# shupito.net
KiCad netlist of a schematic drawn in EAGLE
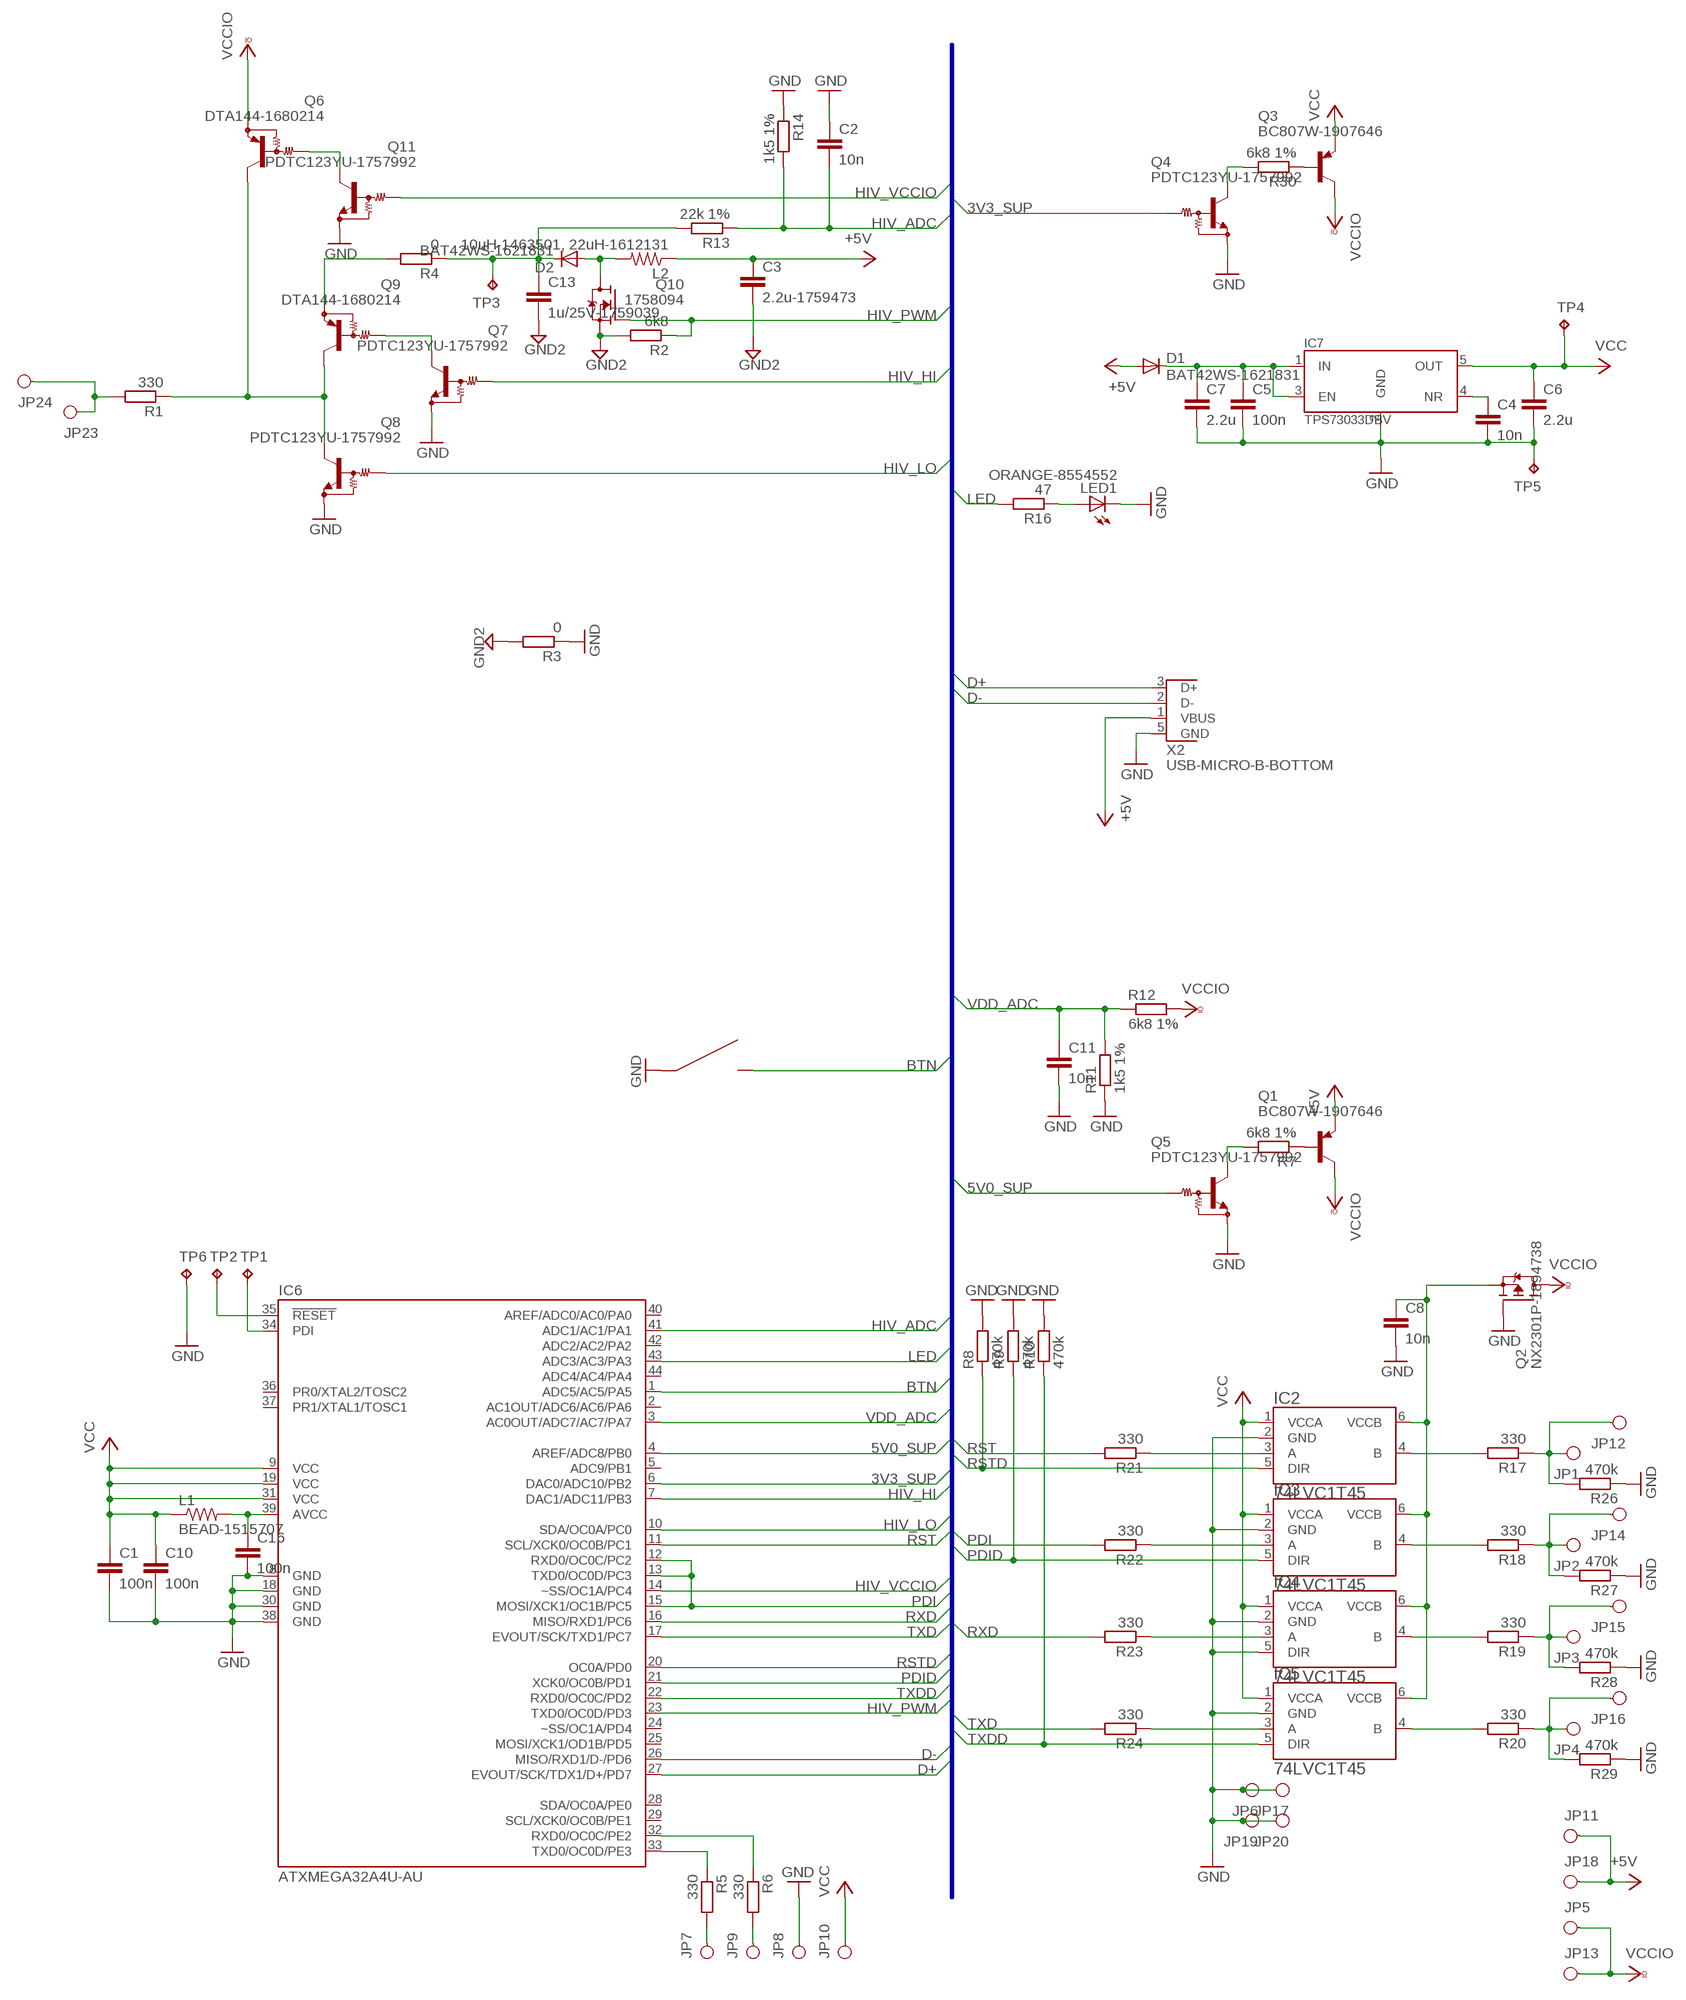
[diagram p0: schematic, sheet 1]

(export (version "E")
  (design (tool "Eeschema 10.0.6"))
  (components
    (comp (ref "C1")
      (value "100n")
      (footprint "eagle-import:C0603K")
      (libsource (lib "eagle-import") (part "C-EUC0603K"))
    )
    (comp (ref "C2")
      (value "10n")
      (footprint "eagle-import:C0603K")
      (libsource (lib "eagle-import") (part "C-EUC0603K"))
    )
    (comp (ref "C3")
      (value "2.2u-1759473")
      (footprint "eagle-import:C0603K")
      (libsource (lib "eagle-import") (part "C-EUC0603K"))
    )
    (comp (ref "C4")
      (value "10n")
      (footprint "eagle-import:C0603K")
      (libsource (lib "eagle-import") (part "C-EUC0603K"))
    )
    (comp (ref "C5")
      (value "100n")
      (footprint "eagle-import:C0603K")
      (libsource (lib "eagle-import") (part "C-EUC0603K"))
    )
    (comp (ref "C6")
      (value "2.2u")
      (footprint "eagle-import:C0603K")
      (libsource (lib "eagle-import") (part "C-EUC0603K"))
    )
    (comp (ref "C7")
      (value "2.2u")
      (footprint "eagle-import:C0603K")
      (libsource (lib "eagle-import") (part "C-EUC0603K"))
    )
    (comp (ref "C8")
      (value "10n")
      (footprint "eagle-import:C0603K")
      (libsource (lib "eagle-import") (part "C-EUC0603K"))
    )
    (comp (ref "C10")
      (value "100n")
      (footprint "eagle-import:C0603K")
      (libsource (lib "eagle-import") (part "C-EUC0603K"))
    )
    (comp (ref "C11")
      (value "10n")
      (footprint "eagle-import:C0603K")
      (libsource (lib "eagle-import") (part "C-EUC0603K"))
    )
    (comp (ref "C13")
      (value "1u/25V-1759039")
      (footprint "eagle-import:C0603K")
      (libsource (lib "eagle-import") (part "C-EUC0603K"))
    )
    (comp (ref "C16")
      (value "100n")
      (footprint "eagle-import:C0603K")
      (libsource (lib "eagle-import") (part "C-EUC0603K"))
    )
    (comp (ref "D1")
      (value "BAT42WS-1621831")
      (footprint "eagle-import:SOD323")
      (libsource (lib "eagle-import") (part "DIODE-SOD323"))
    )
    (comp (ref "D2")
      (value "BAT42WS-1621831")
      (footprint "eagle-import:SOD323")
      (libsource (lib "eagle-import") (part "DIODE-SOD323"))
    )
    (comp (ref "IC2")
      (value "74LVC1T45")
      (footprint "eagle-import:SOT236")
      (libsource (lib "eagle-import") (part "741T45DBVLVC"))
    )
    (comp (ref "IC3")
      (value "74LVC1T45")
      (footprint "eagle-import:SOT236")
      (libsource (lib "eagle-import") (part "741T45DBVLVC"))
    )
    (comp (ref "IC4")
      (value "74LVC1T45")
      (footprint "eagle-import:SOT236")
      (libsource (lib "eagle-import") (part "741T45DBVLVC"))
    )
    (comp (ref "IC5")
      (value "74LVC1T45")
      (footprint "eagle-import:SOT236")
      (libsource (lib "eagle-import") (part "741T45DBVLVC"))
    )
    (comp (ref "IC6")
      (value "ATXMEGA32A4U-AU")
      (footprint "eagle-import:TQFP44")
      (libsource (lib "eagle-import") (part "ATXMEGAA4U-AU32"))
    )
    (comp (ref "IC7")
      (value "TPS73033DBV")
      (footprint "eagle-import:SOT23-DBV")
      (libsource (lib "eagle-import") (part "TPS73033DBV"))
    )
    (comp (ref "JP1")
      (value "PINH1X01SMD")
      (footprint "eagle-import:PINH1X01SMD")
      (libsource (lib "eagle-import") (part "PINH1X01SMD"))
    )
    (comp (ref "JP2")
      (value "PINH1X01SMD")
      (footprint "eagle-import:PINH1X01SMD")
      (libsource (lib "eagle-import") (part "PINH1X01SMD"))
    )
    (comp (ref "JP3")
      (value "PINH1X01SMD")
      (footprint "eagle-import:PINH1X01SMD")
      (libsource (lib "eagle-import") (part "PINH1X01SMD"))
    )
    (comp (ref "JP4")
      (value "PINH1X01SMD")
      (footprint "eagle-import:PINH1X01SMD")
      (libsource (lib "eagle-import") (part "PINH1X01SMD"))
    )
    (comp (ref "JP5")
      (value "PINH1X01SMD")
      (footprint "eagle-import:PINH1X01SMD")
      (libsource (lib "eagle-import") (part "PINH1X01SMD"))
    )
    (comp (ref "JP6")
      (value "PINH1X01SMD")
      (footprint "eagle-import:PINH1X01SMD")
      (libsource (lib "eagle-import") (part "PINH1X01SMD"))
    )
    (comp (ref "JP7")
      (value "PINH1X01SMD")
      (footprint "eagle-import:PINH1X01SMD")
      (libsource (lib "eagle-import") (part "PINH1X01SMD"))
    )
    (comp (ref "JP8")
      (value "PINH1X01SMD")
      (footprint "eagle-import:PINH1X01SMD")
      (libsource (lib "eagle-import") (part "PINH1X01SMD"))
    )
    (comp (ref "JP9")
      (value "PINH1X01SMD")
      (footprint "eagle-import:PINH1X01SMD")
      (libsource (lib "eagle-import") (part "PINH1X01SMD"))
    )
    (comp (ref "JP10")
      (value "PINH1X01SMD")
      (footprint "eagle-import:PINH1X01SMD")
      (libsource (lib "eagle-import") (part "PINH1X01SMD"))
    )
    (comp (ref "JP11")
      (value "PINH1X01SMD")
      (footprint "eagle-import:PINH1X01SMD")
      (libsource (lib "eagle-import") (part "PINH1X01SMD"))
    )
    (comp (ref "JP12")
      (value "PINH1X01SMD")
      (footprint "eagle-import:PINH1X01SMD")
      (libsource (lib "eagle-import") (part "PINH1X01SMD"))
    )
    (comp (ref "JP13")
      (value "PINH1X01SMD")
      (footprint "eagle-import:PINH1X01SMD")
      (libsource (lib "eagle-import") (part "PINH1X01SMD"))
    )
    (comp (ref "JP14")
      (value "PINH1X01SMD")
      (footprint "eagle-import:PINH1X01SMD")
      (libsource (lib "eagle-import") (part "PINH1X01SMD"))
    )
    (comp (ref "JP15")
      (value "PINH1X01SMD")
      (footprint "eagle-import:PINH1X01SMD")
      (libsource (lib "eagle-import") (part "PINH1X01SMD"))
    )
    (comp (ref "JP16")
      (value "PINH1X01SMD")
      (footprint "eagle-import:PINH1X01SMD")
      (libsource (lib "eagle-import") (part "PINH1X01SMD"))
    )
    (comp (ref "JP17")
      (value "PINH1X01SMD")
      (footprint "eagle-import:PINH1X01SMD")
      (libsource (lib "eagle-import") (part "PINH1X01SMD"))
    )
    (comp (ref "JP18")
      (value "PINH1X01SMD")
      (footprint "eagle-import:PINH1X01SMD")
      (libsource (lib "eagle-import") (part "PINH1X01SMD"))
    )
    (comp (ref "JP19")
      (value "PINH1X01SMD")
      (footprint "eagle-import:PINH1X01SMD")
      (libsource (lib "eagle-import") (part "PINH1X01SMD"))
    )
    (comp (ref "JP20")
      (value "PINH1X01SMD")
      (footprint "eagle-import:PINH1X01SMD")
      (libsource (lib "eagle-import") (part "PINH1X01SMD"))
    )
    (comp (ref "JP23")
      (value "PINH1X01SMD")
      (footprint "eagle-import:PINH1X01SMD")
      (libsource (lib "eagle-import") (part "PINH1X01SMD"))
    )
    (comp (ref "JP24")
      (value "PINH1X01SMD")
      (footprint "eagle-import:PINH1X01SMD")
      (libsource (lib "eagle-import") (part "PINH1X01SMD"))
    )
    (comp (ref "L1")
      (value "BEAD-1515707")
      (footprint "eagle-import:R0603")
      (libsource (lib "eagle-import") (part "R-US_R0603"))
    )
    (comp (ref "L2")
      (value "10uH-1463501, 22uH-1612131")
      (footprint "eagle-import:R0805")
      (libsource (lib "eagle-import") (part "R-US_R0805"))
    )
    (comp (ref "LED1")
      (value "ORANGE-8554552")
      (footprint "eagle-import:CHIPLED_0603")
      (libsource (lib "eagle-import") (part "LEDCHIPLED_0603"))
    )
    (comp (ref "Q1")
      (value "BC807W-1907646")
      (footprint "eagle-import:SOT323-BEC")
      (libsource (lib "eagle-import") (part "BC807W"))
    )
    (comp (ref "Q2")
      (value "NX2301P-1894738")
      (footprint "eagle-import:SOT23")
      (libsource (lib "eagle-import") (part "P-MOSFET-SOT23-GSD"))
    )
    (comp (ref "Q3")
      (value "BC807W-1907646")
      (footprint "eagle-import:SOT323-BEC")
      (libsource (lib "eagle-import") (part "BC807W"))
    )
    (comp (ref "Q4")
      (value "PDTC123YU-1757992")
      (footprint "eagle-import:SOT323")
      (libsource (lib "eagle-import") (part "NPN-BIAS-SOT323-BEC"))
    )
    (comp (ref "Q5")
      (value "PDTC123YU-1757992")
      (footprint "eagle-import:SOT323")
      (libsource (lib "eagle-import") (part "NPN-BIAS-SOT323-BEC"))
    )
    (comp (ref "Q6")
      (value "DTA144-1680214")
      (footprint "eagle-import:SOT323")
      (libsource (lib "eagle-import") (part "PNP-BIAS-SOT323-BEC"))
    )
    (comp (ref "Q7")
      (value "PDTC123YU-1757992")
      (footprint "eagle-import:SOT323")
      (libsource (lib "eagle-import") (part "NPN-BIAS-SOT323-BEC"))
    )
    (comp (ref "Q8")
      (value "PDTC123YU-1757992")
      (footprint "eagle-import:SOT323")
      (libsource (lib "eagle-import") (part "NPN-BIAS-SOT323-BEC"))
    )
    (comp (ref "Q9")
      (value "DTA144-1680214")
      (footprint "eagle-import:SOT323")
      (libsource (lib "eagle-import") (part "PNP-BIAS-SOT323-BEC"))
    )
    (comp (ref "Q10")
      (value "1758094")
      (footprint "eagle-import:SOT323")
      (libsource (lib "eagle-import") (part "N-MOSFET-SOT323-GSD"))
    )
    (comp (ref "Q11")
      (value "PDTC123YU-1757992")
      (footprint "eagle-import:SOT323")
      (libsource (lib "eagle-import") (part "NPN-BIAS-SOT323-BEC"))
    )
    (comp (ref "R1")
      (value "330")
      (footprint "eagle-import:R0603")
      (libsource (lib "eagle-import") (part "R-EU_R0603"))
    )
    (comp (ref "R2")
      (value "6k8")
      (footprint "eagle-import:R0603")
      (libsource (lib "eagle-import") (part "R-EU_R0603"))
    )
    (comp (ref "R3")
      (value "0")
      (footprint "eagle-import:R1206")
      (libsource (lib "eagle-import") (part "R-EU_R1206"))
    )
    (comp (ref "R4")
      (value "0")
      (footprint "eagle-import:R1206")
      (libsource (lib "eagle-import") (part "R-EU_R1206"))
    )
    (comp (ref "R5")
      (value "330")
      (footprint "eagle-import:R0603")
      (libsource (lib "eagle-import") (part "R-EU_R0603"))
    )
    (comp (ref "R6")
      (value "330")
      (footprint "eagle-import:R0603")
      (libsource (lib "eagle-import") (part "R-EU_R0603"))
    )
    (comp (ref "R7")
      (value "6k8 1%")
      (footprint "eagle-import:R0603")
      (libsource (lib "eagle-import") (part "R-EU_R0603"))
    )
    (comp (ref "R8")
      (value "470k")
      (footprint "eagle-import:R0603")
      (libsource (lib "eagle-import") (part "R-EU_R0603"))
    )
    (comp (ref "R9")
      (value "470k")
      (footprint "eagle-import:R0603")
      (libsource (lib "eagle-import") (part "R-EU_R0603"))
    )
    (comp (ref "R10")
      (value "470k")
      (footprint "eagle-import:R0603")
      (libsource (lib "eagle-import") (part "R-EU_R0603"))
    )
    (comp (ref "R11")
      (value "1k5 1%")
      (footprint "eagle-import:R0603")
      (libsource (lib "eagle-import") (part "R-EU_R0603"))
    )
    (comp (ref "R12")
      (value "6k8 1%")
      (footprint "eagle-import:R0603")
      (libsource (lib "eagle-import") (part "R-EU_R0603"))
    )
    (comp (ref "R13")
      (value "22k 1%")
      (footprint "eagle-import:R0603")
      (libsource (lib "eagle-import") (part "R-EU_R0603"))
    )
    (comp (ref "R14")
      (value "1k5 1%")
      (footprint "eagle-import:R0603")
      (libsource (lib "eagle-import") (part "R-EU_R0603"))
    )
    (comp (ref "R16")
      (value "47")
      (footprint "eagle-import:R0603")
      (libsource (lib "eagle-import") (part "R-EU_R0603"))
    )
    (comp (ref "R17")
      (value "330")
      (footprint "eagle-import:R0603")
      (libsource (lib "eagle-import") (part "R-EU_R0603"))
    )
    (comp (ref "R18")
      (value "330")
      (footprint "eagle-import:R0603")
      (libsource (lib "eagle-import") (part "R-EU_R0603"))
    )
    (comp (ref "R19")
      (value "330")
      (footprint "eagle-import:R0603")
      (libsource (lib "eagle-import") (part "R-EU_R0603"))
    )
    (comp (ref "R20")
      (value "330")
      (footprint "eagle-import:R0603")
      (libsource (lib "eagle-import") (part "R-EU_R0603"))
    )
    (comp (ref "R21")
      (value "330")
      (footprint "eagle-import:R0603")
      (libsource (lib "eagle-import") (part "R-EU_R0603"))
    )
    (comp (ref "R22")
      (value "330")
      (footprint "eagle-import:R0603")
      (libsource (lib "eagle-import") (part "R-EU_R0603"))
    )
    (comp (ref "R23")
      (value "330")
      (footprint "eagle-import:R0603")
      (libsource (lib "eagle-import") (part "R-EU_R0603"))
    )
    (comp (ref "R24")
      (value "330")
      (footprint "eagle-import:R0603")
      (libsource (lib "eagle-import") (part "R-EU_R0603"))
    )
    (comp (ref "R26")
      (value "470k")
      (footprint "eagle-import:R0603")
      (libsource (lib "eagle-import") (part "R-EU_R0603"))
    )
    (comp (ref "R27")
      (value "470k")
      (footprint "eagle-import:R0603")
      (libsource (lib "eagle-import") (part "R-EU_R0603"))
    )
    (comp (ref "R28")
      (value "470k")
      (footprint "eagle-import:R0603")
      (libsource (lib "eagle-import") (part "R-EU_R0603"))
    )
    (comp (ref "R29")
      (value "470k")
      (footprint "eagle-import:R0603")
      (libsource (lib "eagle-import") (part "R-EU_R0603"))
    )
    (comp (ref "R30")
      (value "6k8 1%")
      (footprint "eagle-import:R0603")
      (libsource (lib "eagle-import") (part "R-EU_R0603"))
    )
    (comp (ref "S1")
      (value "KSS241G")
      (footprint "eagle-import:KSS-G")
      (libsource (lib "eagle-import") (part "KSSG241"))
    )
    (comp (ref "TP1")
      (value "TPTP15SQ")
      (footprint "eagle-import:TP15SQ")
      (libsource (lib "eagle-import") (part "TPTP15SQ"))
    )
    (comp (ref "TP2")
      (value "TPTP15SQ")
      (footprint "eagle-import:TP15SQ")
      (libsource (lib "eagle-import") (part "TPTP15SQ"))
    )
    (comp (ref "TP3")
      (value "TPTP15SQ")
      (footprint "eagle-import:TP15SQ")
      (libsource (lib "eagle-import") (part "TPTP15SQ"))
    )
    (comp (ref "TP4")
      (value "TPTP15SQ")
      (footprint "eagle-import:TP15SQ")
      (libsource (lib "eagle-import") (part "TPTP15SQ"))
    )
    (comp (ref "TP5")
      (value "TPTP15SQ")
      (footprint "eagle-import:TP15SQ")
      (libsource (lib "eagle-import") (part "TPTP15SQ"))
    )
    (comp (ref "TP6")
      (value "TPTP15SQ")
      (footprint "eagle-import:TP15SQ")
      (libsource (lib "eagle-import") (part "TPTP15SQ"))
    )
    (comp (ref "X2")
      (value "USB-MICRO-B-BOTTOM")
      (footprint "eagle-import:USB-MICRO-B-BOTTOM-MOLEX")
      (libsource (lib "eagle-import") (part "USB-MICRO-B-BOTTOM"))
    )
  )
  (nets
    (net (code "1") (name "+5V") (class "Default")
      (node (ref "C3") (pin "1") (pinfunction "1_1") (pintype "passive"))
      (node (ref "D1") (pin "A") (pinfunction "A_A") (pintype "passive"))
      (node (ref "JP11") (pin "1") (pinfunction "1_1") (pintype "passive"))
      (node (ref "JP18") (pin "1") (pinfunction "1_1") (pintype "passive"))
      (node (ref "L2") (pin "1") (pinfunction "1_1") (pintype "passive"))
      (node (ref "Q1") (pin "2") (pinfunction "E_2") (pintype "passive"))
      (node (ref "X2") (pin "1") (pinfunction "VBUS_1") (pintype "passive"))
    )
    (net (code "2") (name "/3V3_SUP") (class "Default")
      (node (ref "IC6") (pin "6") (pinfunction "DAC0/ADC10/PB2_6") (pintype "bidirectional"))
      (node (ref "Q4") (pin "1") (pinfunction "B_1") (pintype "passive"))
    )
    (net (code "3") (name "/5V0_SUP") (class "Default")
      (node (ref "IC6") (pin "4") (pinfunction "AREF/ADC8/PB0_4") (pintype "bidirectional"))
      (node (ref "Q5") (pin "1") (pinfunction "B_1") (pintype "passive"))
    )
    (net (code "4") (name "/BTN") (class "Default")
      (node (ref "IC6") (pin "1") (pinfunction "ADC5/AC5/PA5_1") (pintype "bidirectional"))
      (node (ref "S1") (pin "2") (pinfunction "P$2_2") (pintype "passive"))
    )
    (net (code "5") (name "/D+") (class "Default")
      (node (ref "IC6") (pin "27") (pinfunction "EVOUT/SCK/TDX1/D+/PD7_27") (pintype "bidirectional"))
      (node (ref "X2") (pin "3") (pinfunction "D+_3") (pintype "bidirectional"))
    )
    (net (code "6") (name "/D-") (class "Default")
      (node (ref "IC6") (pin "26") (pinfunction "MISO/RXD1/D-/PD6_26") (pintype "bidirectional"))
      (node (ref "X2") (pin "2") (pinfunction "D-_2") (pintype "bidirectional"))
    )
    (net (code "7") (name "/HIV_ADC") (class "Default")
      (node (ref "C2") (pin "2") (pinfunction "2_2") (pintype "passive"))
      (node (ref "IC6") (pin "41") (pinfunction "ADC1/AC1/PA1_41") (pintype "bidirectional"))
      (node (ref "R13") (pin "1") (pinfunction "1_1") (pintype "passive"))
      (node (ref "R14") (pin "2") (pinfunction "2_2") (pintype "passive"))
    )
    (net (code "8") (name "/HIV_HI") (class "Default")
      (node (ref "IC6") (pin "7") (pinfunction "DAC1/ADC11/PB3_7") (pintype "bidirectional"))
      (node (ref "Q7") (pin "1") (pinfunction "B_1") (pintype "passive"))
    )
    (net (code "9") (name "/HIV_LO") (class "Default")
      (node (ref "IC6") (pin "10") (pinfunction "SDA/OC0A/PC0_10") (pintype "bidirectional"))
      (node (ref "Q8") (pin "1") (pinfunction "B_1") (pintype "passive"))
    )
    (net (code "10") (name "/HIV_PWM") (class "Default")
      (node (ref "IC6") (pin "23") (pinfunction "TXD0/OC0D/PD3_23") (pintype "bidirectional"))
      (node (ref "Q10") (pin "1") (pinfunction "G_1") (pintype "passive"))
      (node (ref "R2") (pin "1") (pinfunction "1_1") (pintype "passive"))
    )
    (net (code "11") (name "/HIV_VCCIO") (class "Default")
      (node (ref "IC6") (pin "14") (pinfunction "~{SS/OC1A/PC4}_14") (pintype "bidirectional"))
      (node (ref "Q11") (pin "1") (pinfunction "B_1") (pintype "passive"))
    )
    (net (code "12") (name "/LED") (class "Default")
      (node (ref "IC6") (pin "43") (pinfunction "ADC3/AC3/PA3_43") (pintype "bidirectional"))
      (node (ref "R16") (pin "2") (pinfunction "2_2") (pintype "passive"))
    )
    (net (code "13") (name "/PDI") (class "Default")
      (node (ref "IC6") (pin "12") (pinfunction "RXD0/OC0C/PC2_12") (pintype "bidirectional"))
      (node (ref "IC6") (pin "13") (pinfunction "TXD0/OC0D/PC3_13") (pintype "bidirectional"))
      (node (ref "IC6") (pin "15") (pinfunction "MOSI/XCK1/OC1B/PC5_15") (pintype "bidirectional"))
      (node (ref "R22") (pin "2") (pinfunction "2_2") (pintype "passive"))
    )
    (net (code "14") (name "/PDID") (class "Default")
      (node (ref "IC3") (pin "5") (pinfunction "DIR_5") (pintype "input"))
      (node (ref "IC6") (pin "21") (pinfunction "XCK0/OC0B/PD1_21") (pintype "bidirectional"))
      (node (ref "R9") (pin "1") (pinfunction "1_1") (pintype "passive"))
    )
    (net (code "15") (name "/RST") (class "Default")
      (node (ref "IC6") (pin "11") (pinfunction "SCL/XCK0/OC0B/PC1_11") (pintype "bidirectional"))
      (node (ref "R21") (pin "2") (pinfunction "2_2") (pintype "passive"))
    )
    (net (code "16") (name "/RSTD") (class "Default")
      (node (ref "IC2") (pin "5") (pinfunction "DIR_5") (pintype "input"))
      (node (ref "IC6") (pin "20") (pinfunction "OC0A/PD0_20") (pintype "bidirectional"))
      (node (ref "R8") (pin "1") (pinfunction "1_1") (pintype "passive"))
    )
    (net (code "17") (name "/RXD") (class "Default")
      (node (ref "IC6") (pin "16") (pinfunction "MISO/RXD1/PC6_16") (pintype "bidirectional"))
      (node (ref "R23") (pin "2") (pinfunction "2_2") (pintype "passive"))
    )
    (net (code "18") (name "/TXD") (class "Default")
      (node (ref "IC6") (pin "17") (pinfunction "EVOUT/SCK/TXD1/PC7_17") (pintype "bidirectional"))
      (node (ref "R24") (pin "2") (pinfunction "2_2") (pintype "passive"))
    )
    (net (code "19") (name "/TXDD") (class "Default")
      (node (ref "IC5") (pin "5") (pinfunction "DIR_5") (pintype "input"))
      (node (ref "IC6") (pin "22") (pinfunction "RXD0/OC0C/PD2_22") (pintype "bidirectional"))
      (node (ref "R10") (pin "1") (pinfunction "1_1") (pintype "passive"))
    )
    (net (code "20") (name "/VDD_ADC") (class "Default")
      (node (ref "C11") (pin "1") (pinfunction "1_1") (pintype "passive"))
      (node (ref "IC6") (pin "3") (pinfunction "AC0OUT/ADC7/AC7/PA7_3") (pintype "bidirectional"))
      (node (ref "R11") (pin "2") (pinfunction "2_2") (pintype "passive"))
      (node (ref "R12") (pin "1") (pinfunction "1_1") (pintype "passive"))
    )
    (net (code "21") (name "GND") (class "Default")
      (node (ref "C1") (pin "2") (pinfunction "2_2") (pintype "passive"))
      (node (ref "C10") (pin "2") (pinfunction "2_2") (pintype "passive"))
      (node (ref "C11") (pin "2") (pinfunction "2_2") (pintype "passive"))
      (node (ref "C16") (pin "2") (pinfunction "2_2") (pintype "passive"))
      (node (ref "C2") (pin "1") (pinfunction "1_1") (pintype "passive"))
      (node (ref "C4") (pin "2") (pinfunction "2_2") (pintype "passive"))
      (node (ref "C5") (pin "2") (pinfunction "2_2") (pintype "passive"))
      (node (ref "C6") (pin "2") (pinfunction "2_2") (pintype "passive"))
      (node (ref "C7") (pin "2") (pinfunction "2_2") (pintype "passive"))
      (node (ref "C8") (pin "2") (pinfunction "2_2") (pintype "passive"))
      (node (ref "IC2") (pin "2") (pinfunction "GND_2") (pintype "passive"))
      (node (ref "IC3") (pin "2") (pinfunction "GND_2") (pintype "passive"))
      (node (ref "IC4") (pin "2") (pinfunction "GND_2") (pintype "passive"))
      (node (ref "IC4") (pin "5") (pinfunction "DIR_5") (pintype "input"))
      (node (ref "IC5") (pin "2") (pinfunction "GND_2") (pintype "passive"))
      (node (ref "IC6") (pin "18") (pinfunction "GND_18") (pintype "passive"))
      (node (ref "IC6") (pin "30") (pinfunction "GND_30") (pintype "passive"))
      (node (ref "IC6") (pin "38") (pinfunction "GND_38") (pintype "passive"))
      (node (ref "IC6") (pin "8") (pinfunction "GND_8") (pintype "passive"))
      (node (ref "IC7") (pin "2") (pinfunction "GND_2") (pintype "passive"))
      (node (ref "JP17") (pin "1") (pinfunction "1_1") (pintype "passive"))
      (node (ref "JP19") (pin "1") (pinfunction "1_1") (pintype "passive"))
      (node (ref "JP20") (pin "1") (pinfunction "1_1") (pintype "passive"))
      (node (ref "JP6") (pin "1") (pinfunction "1_1") (pintype "passive"))
      (node (ref "JP8") (pin "1") (pinfunction "1_1") (pintype "passive"))
      (node (ref "LED1") (pin "C") (pinfunction "C_C") (pintype "passive"))
      (node (ref "Q11") (pin "2") (pinfunction "E_2") (pintype "passive"))
      (node (ref "Q2") (pin "1") (pinfunction "G_1") (pintype "passive"))
      (node (ref "Q4") (pin "2") (pinfunction "E_2") (pintype "passive"))
      (node (ref "Q5") (pin "2") (pinfunction "E_2") (pintype "passive"))
      (node (ref "Q7") (pin "2") (pinfunction "E_2") (pintype "passive"))
      (node (ref "Q8") (pin "2") (pinfunction "E_2") (pintype "passive"))
      (node (ref "R10") (pin "2") (pinfunction "2_2") (pintype "passive"))
      (node (ref "R11") (pin "1") (pinfunction "1_1") (pintype "passive"))
      (node (ref "R14") (pin "1") (pinfunction "1_1") (pintype "passive"))
      (node (ref "R26") (pin "1") (pinfunction "1_1") (pintype "passive"))
      (node (ref "R27") (pin "1") (pinfunction "1_1") (pintype "passive"))
      (node (ref "R28") (pin "1") (pinfunction "1_1") (pintype "passive"))
      (node (ref "R29") (pin "1") (pinfunction "1_1") (pintype "passive"))
      (node (ref "R3") (pin "1") (pinfunction "1_1") (pintype "passive"))
      (node (ref "R8") (pin "2") (pinfunction "2_2") (pintype "passive"))
      (node (ref "R9") (pin "2") (pinfunction "2_2") (pintype "passive"))
      (node (ref "S1") (pin "1") (pinfunction "P$1_1") (pintype "passive"))
      (node (ref "TP5") (pin "TP") (pinfunction "TP_TP") (pintype "input"))
      (node (ref "TP6") (pin "TP") (pinfunction "TP_TP") (pintype "input"))
      (node (ref "X2") (pin "5") (pinfunction "GND_5") (pintype "passive"))
    )
    (net (code "22") (name "GND2") (class "Default")
      (node (ref "C13") (pin "2") (pinfunction "2_2") (pintype "passive"))
      (node (ref "C3") (pin "2") (pinfunction "2_2") (pintype "passive"))
      (node (ref "Q10") (pin "2") (pinfunction "S_2") (pintype "passive"))
      (node (ref "R2") (pin "2") (pinfunction "2_2") (pintype "passive"))
      (node (ref "R3") (pin "2") (pinfunction "2_2") (pintype "passive"))
    )
    (net (code "23") (name "Net-(C13-Pad1)") (class "Default")
      (node (ref "C13") (pin "1") (pinfunction "1_1") (pintype "passive"))
      (node (ref "D2") (pin "C") (pinfunction "C_C") (pintype "passive"))
      (node (ref "R13") (pin "2") (pinfunction "2_2") (pintype "passive"))
      (node (ref "R4") (pin "1") (pinfunction "1_1") (pintype "passive"))
      (node (ref "TP3") (pin "TP") (pinfunction "TP_TP") (pintype "input"))
    )
    (net (code "24") (name "Net-(IC2-A)") (class "Default")
      (node (ref "IC2") (pin "3") (pinfunction "A_3") (pintype "bidirectional"))
      (node (ref "R21") (pin "1") (pinfunction "1_1") (pintype "passive"))
    )
    (net (code "25") (name "Net-(IC2-B)") (class "Default")
      (node (ref "IC2") (pin "4") (pinfunction "B_4") (pintype "bidirectional"))
      (node (ref "R17") (pin "2") (pinfunction "2_2") (pintype "passive"))
    )
    (net (code "26") (name "Net-(IC2-VCCB)") (class "Default")
      (node (ref "C8") (pin "1") (pinfunction "1_1") (pintype "passive"))
      (node (ref "IC2") (pin "6") (pinfunction "VCCB_6") (pintype "passive"))
      (node (ref "IC3") (pin "6") (pinfunction "VCCB_6") (pintype "passive"))
      (node (ref "IC4") (pin "6") (pinfunction "VCCB_6") (pintype "passive"))
      (node (ref "IC5") (pin "6") (pinfunction "VCCB_6") (pintype "passive"))
      (node (ref "Q2") (pin "2") (pinfunction "S_2") (pintype "passive"))
    )
    (net (code "27") (name "Net-(IC3-A)") (class "Default")
      (node (ref "IC3") (pin "3") (pinfunction "A_3") (pintype "bidirectional"))
      (node (ref "R22") (pin "1") (pinfunction "1_1") (pintype "passive"))
    )
    (net (code "28") (name "Net-(IC3-B)") (class "Default")
      (node (ref "IC3") (pin "4") (pinfunction "B_4") (pintype "bidirectional"))
      (node (ref "R18") (pin "2") (pinfunction "2_2") (pintype "passive"))
    )
    (net (code "29") (name "Net-(IC4-A)") (class "Default")
      (node (ref "IC4") (pin "3") (pinfunction "A_3") (pintype "bidirectional"))
      (node (ref "R23") (pin "1") (pinfunction "1_1") (pintype "passive"))
    )
    (net (code "30") (name "Net-(IC4-B)") (class "Default")
      (node (ref "IC4") (pin "4") (pinfunction "B_4") (pintype "bidirectional"))
      (node (ref "R19") (pin "2") (pinfunction "2_2") (pintype "passive"))
    )
    (net (code "31") (name "Net-(IC5-A)") (class "Default")
      (node (ref "IC5") (pin "3") (pinfunction "A_3") (pintype "bidirectional"))
      (node (ref "R24") (pin "1") (pinfunction "1_1") (pintype "passive"))
    )
    (net (code "32") (name "Net-(IC5-B)") (class "Default")
      (node (ref "IC5") (pin "4") (pinfunction "B_4") (pintype "bidirectional"))
      (node (ref "R20") (pin "2") (pinfunction "2_2") (pintype "passive"))
    )
    (net (code "33") (name "Net-(IC6-AVCC)") (class "Default")
      (node (ref "C16") (pin "1") (pinfunction "1_1") (pintype "passive"))
      (node (ref "IC6") (pin "39") (pinfunction "AVCC_39") (pintype "passive"))
      (node (ref "L1") (pin "2") (pinfunction "2_2") (pintype "passive"))
    )
    (net (code "34") (name "Net-(IC6-PDI)") (class "Default")
      (node (ref "IC6") (pin "34") (pinfunction "PDI_34") (pintype "bidirectional"))
      (node (ref "TP1") (pin "TP") (pinfunction "TP_TP") (pintype "input"))
    )
    (net (code "35") (name "Net-(IC6-RXD0{slash}OC0C{slash}PE2)") (class "Default")
      (node (ref "IC6") (pin "32") (pinfunction "RXD0/OC0C/PE2_32") (pintype "bidirectional"))
      (node (ref "R6") (pin "1") (pinfunction "1_1") (pintype "passive"))
    )
    (net (code "36") (name "Net-(IC6-TXD0{slash}OC0D{slash}PE3)") (class "Default")
      (node (ref "IC6") (pin "33") (pinfunction "TXD0/OC0D/PE3_33") (pintype "bidirectional"))
      (node (ref "R5") (pin "1") (pinfunction "1_1") (pintype "passive"))
    )
    (net (code "37") (name "Net-(IC6-~{RESET})") (class "Default")
      (node (ref "IC6") (pin "35") (pinfunction "~{RESET}_35") (pintype "input"))
      (node (ref "TP2") (pin "TP") (pinfunction "TP_TP") (pintype "input"))
    )
    (net (code "38") (name "Net-(IC7-EN)") (class "Default")
      (node (ref "C5") (pin "1") (pinfunction "1_1") (pintype "passive"))
      (node (ref "C7") (pin "1") (pinfunction "1_1") (pintype "passive"))
      (node (ref "D1") (pin "C") (pinfunction "C_C") (pintype "passive"))
      (node (ref "IC7") (pin "1") (pinfunction "IN_1") (pintype "passive"))
      (node (ref "IC7") (pin "3") (pinfunction "EN_3") (pintype "input"))
    )
    (net (code "39") (name "Net-(IC7-NR)") (class "Default")
      (node (ref "C4") (pin "1") (pinfunction "1_1") (pintype "passive"))
      (node (ref "IC7") (pin "4") (pinfunction "NR_4") (pintype "passive"))
    )
    (net (code "40") (name "Net-(JP1-Pad1)") (class "Default")
      (node (ref "JP1") (pin "1") (pinfunction "1_1") (pintype "passive"))
      (node (ref "JP12") (pin "1") (pinfunction "1_1") (pintype "passive"))
      (node (ref "R17") (pin "1") (pinfunction "1_1") (pintype "passive"))
      (node (ref "R26") (pin "2") (pinfunction "2_2") (pintype "passive"))
    )
    (net (code "41") (name "Net-(JP7-Pad1)") (class "Default")
      (node (ref "JP7") (pin "1") (pinfunction "1_1") (pintype "passive"))
      (node (ref "R5") (pin "2") (pinfunction "2_2") (pintype "passive"))
    )
    (net (code "42") (name "Net-(JP9-Pad1)") (class "Default")
      (node (ref "JP9") (pin "1") (pinfunction "1_1") (pintype "passive"))
      (node (ref "R6") (pin "2") (pinfunction "2_2") (pintype "passive"))
    )
    (net (code "43") (name "Net-(JP14-Pad1)") (class "Default")
      (node (ref "JP14") (pin "1") (pinfunction "1_1") (pintype "passive"))
      (node (ref "JP2") (pin "1") (pinfunction "1_1") (pintype "passive"))
      (node (ref "R18") (pin "1") (pinfunction "1_1") (pintype "passive"))
      (node (ref "R27") (pin "2") (pinfunction "2_2") (pintype "passive"))
    )
    (net (code "44") (name "Net-(JP15-Pad1)") (class "Default")
      (node (ref "JP15") (pin "1") (pinfunction "1_1") (pintype "passive"))
      (node (ref "JP3") (pin "1") (pinfunction "1_1") (pintype "passive"))
      (node (ref "R19") (pin "1") (pinfunction "1_1") (pintype "passive"))
      (node (ref "R28") (pin "2") (pinfunction "2_2") (pintype "passive"))
    )
    (net (code "45") (name "Net-(JP16-Pad1)") (class "Default")
      (node (ref "JP16") (pin "1") (pinfunction "1_1") (pintype "passive"))
      (node (ref "JP4") (pin "1") (pinfunction "1_1") (pintype "passive"))
      (node (ref "R20") (pin "1") (pinfunction "1_1") (pintype "passive"))
      (node (ref "R29") (pin "2") (pinfunction "2_2") (pintype "passive"))
    )
    (net (code "46") (name "Net-(JP23-Pad1)") (class "Default")
      (node (ref "JP23") (pin "1") (pinfunction "1_1") (pintype "passive"))
      (node (ref "JP24") (pin "1") (pinfunction "1_1") (pintype "passive"))
      (node (ref "R1") (pin "2") (pinfunction "2_2") (pintype "passive"))
    )
    (net (code "47") (name "Net-(LED1-PadA)") (class "Default")
      (node (ref "LED1") (pin "A") (pinfunction "A_A") (pintype "passive"))
      (node (ref "R16") (pin "1") (pinfunction "1_1") (pintype "passive"))
    )
    (net (code "48") (name "Net-(Q1-B)") (class "Default")
      (node (ref "Q1") (pin "1") (pinfunction "B_1") (pintype "passive"))
      (node (ref "R7") (pin "1") (pinfunction "1_1") (pintype "passive"))
    )
    (net (code "49") (name "Net-(Q3-B)") (class "Default")
      (node (ref "Q3") (pin "1") (pinfunction "B_1") (pintype "passive"))
      (node (ref "R30") (pin "1") (pinfunction "1_1") (pintype "passive"))
    )
    (net (code "50") (name "Net-(Q4-C)") (class "Default")
      (node (ref "Q4") (pin "3") (pinfunction "C_3") (pintype "passive"))
      (node (ref "R30") (pin "2") (pinfunction "2_2") (pintype "passive"))
    )
    (net (code "51") (name "Net-(Q5-C)") (class "Default")
      (node (ref "Q5") (pin "3") (pinfunction "C_3") (pintype "passive"))
      (node (ref "R7") (pin "2") (pinfunction "2_2") (pintype "passive"))
    )
    (net (code "52") (name "Net-(Q6-C)") (class "Default")
      (node (ref "Q6") (pin "3") (pinfunction "C_3") (pintype "passive"))
      (node (ref "Q8") (pin "3") (pinfunction "C_3") (pintype "passive"))
      (node (ref "Q9") (pin "3") (pinfunction "C_3") (pintype "passive"))
      (node (ref "R1") (pin "1") (pinfunction "1_1") (pintype "passive"))
    )
    (net (code "53") (name "Net-(Q7-C)") (class "Default")
      (node (ref "Q7") (pin "3") (pinfunction "C_3") (pintype "passive"))
      (node (ref "Q9") (pin "1") (pinfunction "B_1") (pintype "passive"))
    )
    (net (code "54") (name "Net-(Q9-E)") (class "Default")
      (node (ref "Q9") (pin "2") (pinfunction "E_2") (pintype "passive"))
      (node (ref "R4") (pin "2") (pinfunction "2_2") (pintype "passive"))
    )
    (net (code "55") (name "Net-(Q10-D)") (class "Default")
      (node (ref "D2") (pin "A") (pinfunction "A_A") (pintype "passive"))
      (node (ref "L2") (pin "2") (pinfunction "2_2") (pintype "passive"))
      (node (ref "Q10") (pin "3") (pinfunction "D_3") (pintype "passive"))
    )
    (net (code "56") (name "Net-(Q11-C)") (class "Default")
      (node (ref "Q11") (pin "3") (pinfunction "C_3") (pintype "passive"))
      (node (ref "Q6") (pin "1") (pinfunction "B_1") (pintype "passive"))
    )
    (net (code "57") (name "VCC") (class "Default")
      (node (ref "C1") (pin "1") (pinfunction "1_1") (pintype "passive"))
      (node (ref "C10") (pin "1") (pinfunction "1_1") (pintype "passive"))
      (node (ref "C6") (pin "1") (pinfunction "1_1") (pintype "passive"))
      (node (ref "IC2") (pin "1") (pinfunction "VCCA_1") (pintype "passive"))
      (node (ref "IC3") (pin "1") (pinfunction "VCCA_1") (pintype "passive"))
      (node (ref "IC4") (pin "1") (pinfunction "VCCA_1") (pintype "passive"))
      (node (ref "IC5") (pin "1") (pinfunction "VCCA_1") (pintype "passive"))
      (node (ref "IC6") (pin "19") (pinfunction "VCC_19") (pintype "passive"))
      (node (ref "IC6") (pin "31") (pinfunction "VCC_31") (pintype "passive"))
      (node (ref "IC6") (pin "9") (pinfunction "VCC_9") (pintype "passive"))
      (node (ref "IC7") (pin "5") (pinfunction "OUT_5") (pintype "passive"))
      (node (ref "JP10") (pin "1") (pinfunction "1_1") (pintype "passive"))
      (node (ref "L1") (pin "1") (pinfunction "1_1") (pintype "passive"))
      (node (ref "Q3") (pin "2") (pinfunction "E_2") (pintype "passive"))
      (node (ref "TP4") (pin "TP") (pinfunction "TP_TP") (pintype "input"))
    )
    (net (code "58") (name "VCCIO") (class "Default")
      (node (ref "JP13") (pin "1") (pinfunction "1_1") (pintype "passive"))
      (node (ref "JP5") (pin "1") (pinfunction "1_1") (pintype "passive"))
      (node (ref "Q1") (pin "3") (pinfunction "C_3") (pintype "passive"))
      (node (ref "Q2") (pin "3") (pinfunction "D_3") (pintype "passive"))
      (node (ref "Q3") (pin "3") (pinfunction "C_3") (pintype "passive"))
      (node (ref "Q6") (pin "2") (pinfunction "E_2") (pintype "passive"))
      (node (ref "R12") (pin "2") (pinfunction "2_2") (pintype "passive"))
    )
    (net (code "59") (name "unconnected-(IC6-AC1OUT{slash}ADC6{slash}AC6{slash}PA6-Pad2)") (class "Default")
      (node (ref "IC6") (pin "2") (pinfunction "AC1OUT/ADC6/AC6/PA6_2") (pintype "bidirectional"))
    )
    (net (code "60") (name "unconnected-(IC6-ADC2{slash}AC2{slash}PA2-Pad42)") (class "Default")
      (node (ref "IC6") (pin "42") (pinfunction "ADC2/AC2/PA2_42") (pintype "bidirectional"))
    )
    (net (code "61") (name "unconnected-(IC6-ADC4{slash}AC4{slash}PA4-Pad44)") (class "Default")
      (node (ref "IC6") (pin "44") (pinfunction "ADC4/AC4/PA4_44") (pintype "bidirectional"))
    )
    (net (code "62") (name "unconnected-(IC6-ADC9{slash}PB1-Pad5)") (class "Default")
      (node (ref "IC6") (pin "5") (pinfunction "ADC9/PB1_5") (pintype "bidirectional"))
    )
    (net (code "63") (name "unconnected-(IC6-AREF{slash}ADC0{slash}AC0{slash}PA0-Pad40)") (class "Default")
      (node (ref "IC6") (pin "40") (pinfunction "AREF/ADC0/AC0/PA0_40") (pintype "bidirectional"))
    )
    (net (code "64") (name "unconnected-(IC6-MOSI{slash}XCK1{slash}OD1B{slash}PD5-Pad25)") (class "Default")
      (node (ref "IC6") (pin "25") (pinfunction "MOSI/XCK1/OD1B/PD5_25") (pintype "bidirectional"))
    )
    (net (code "65") (name "unconnected-(IC6-PR0{slash}XTAL2{slash}TOSC2-Pad36)") (class "Default")
      (node (ref "IC6") (pin "36") (pinfunction "PR0/XTAL2/TOSC2_36") (pintype "passive"))
    )
    (net (code "66") (name "unconnected-(IC6-PR1{slash}XTAL1{slash}TOSC1-Pad37)") (class "Default")
      (node (ref "IC6") (pin "37") (pinfunction "PR1/XTAL1/TOSC1_37") (pintype "passive"))
    )
    (net (code "67") (name "unconnected-(IC6-SCL{slash}XCK0{slash}OC0B{slash}PE1-Pad29)") (class "Default")
      (node (ref "IC6") (pin "29") (pinfunction "SCL/XCK0/OC0B/PE1_29") (pintype "bidirectional"))
    )
    (net (code "68") (name "unconnected-(IC6-SDA{slash}OC0A{slash}PE0-Pad28)") (class "Default")
      (node (ref "IC6") (pin "28") (pinfunction "SDA/OC0A/PE0_28") (pintype "bidirectional"))
    )
    (net (code "69") (name "unconnected-(IC6-~{SS{slash}OC1A{slash}PD4}-Pad24)") (class "Default")
      (node (ref "IC6") (pin "24") (pinfunction "~{SS/OC1A/PD4}_24") (pintype "bidirectional"))
    )
  )
)
